# dc26-dev-board-apa102c.net
KiCad netlist of a schematic drawn in EAGLE
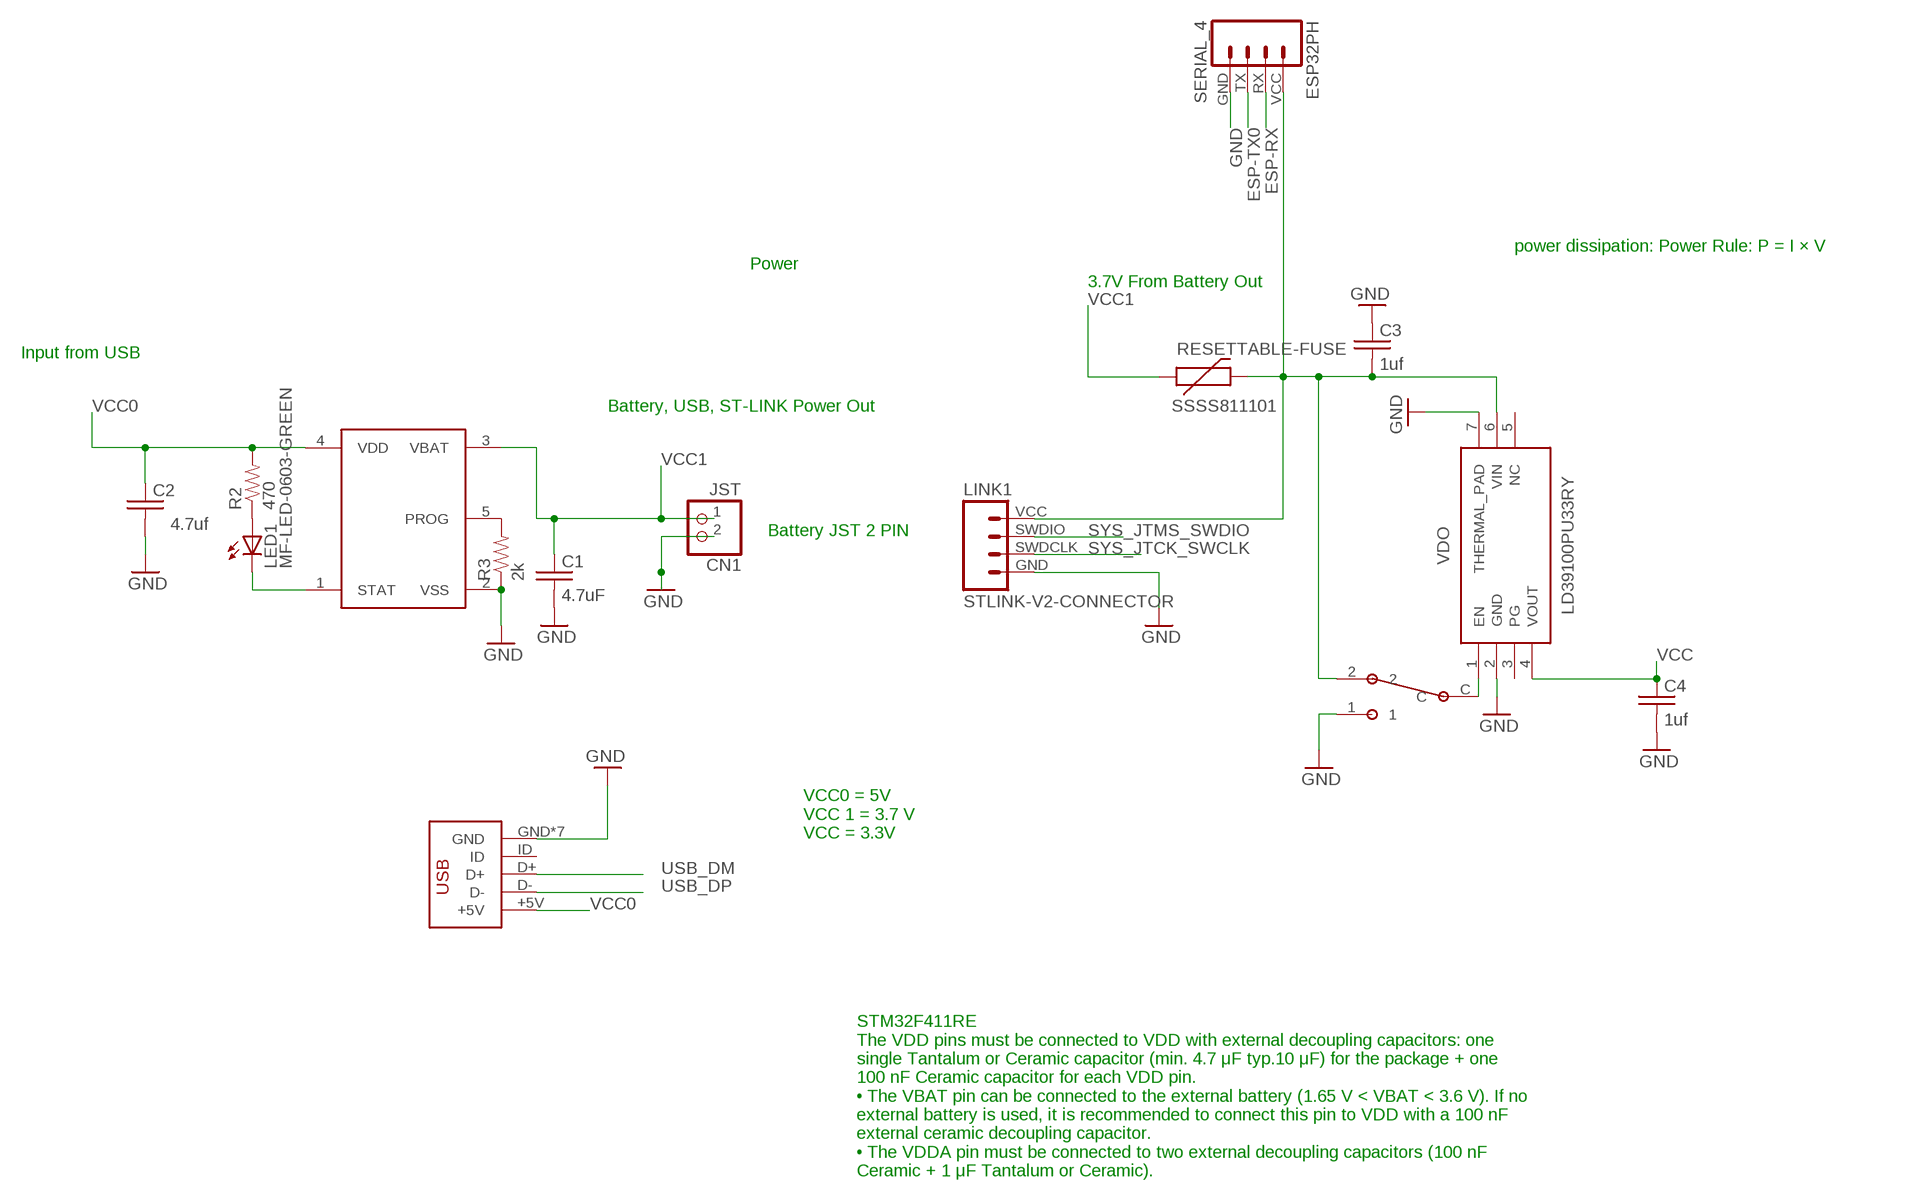
[diagram p0: schematic, sheet 1]
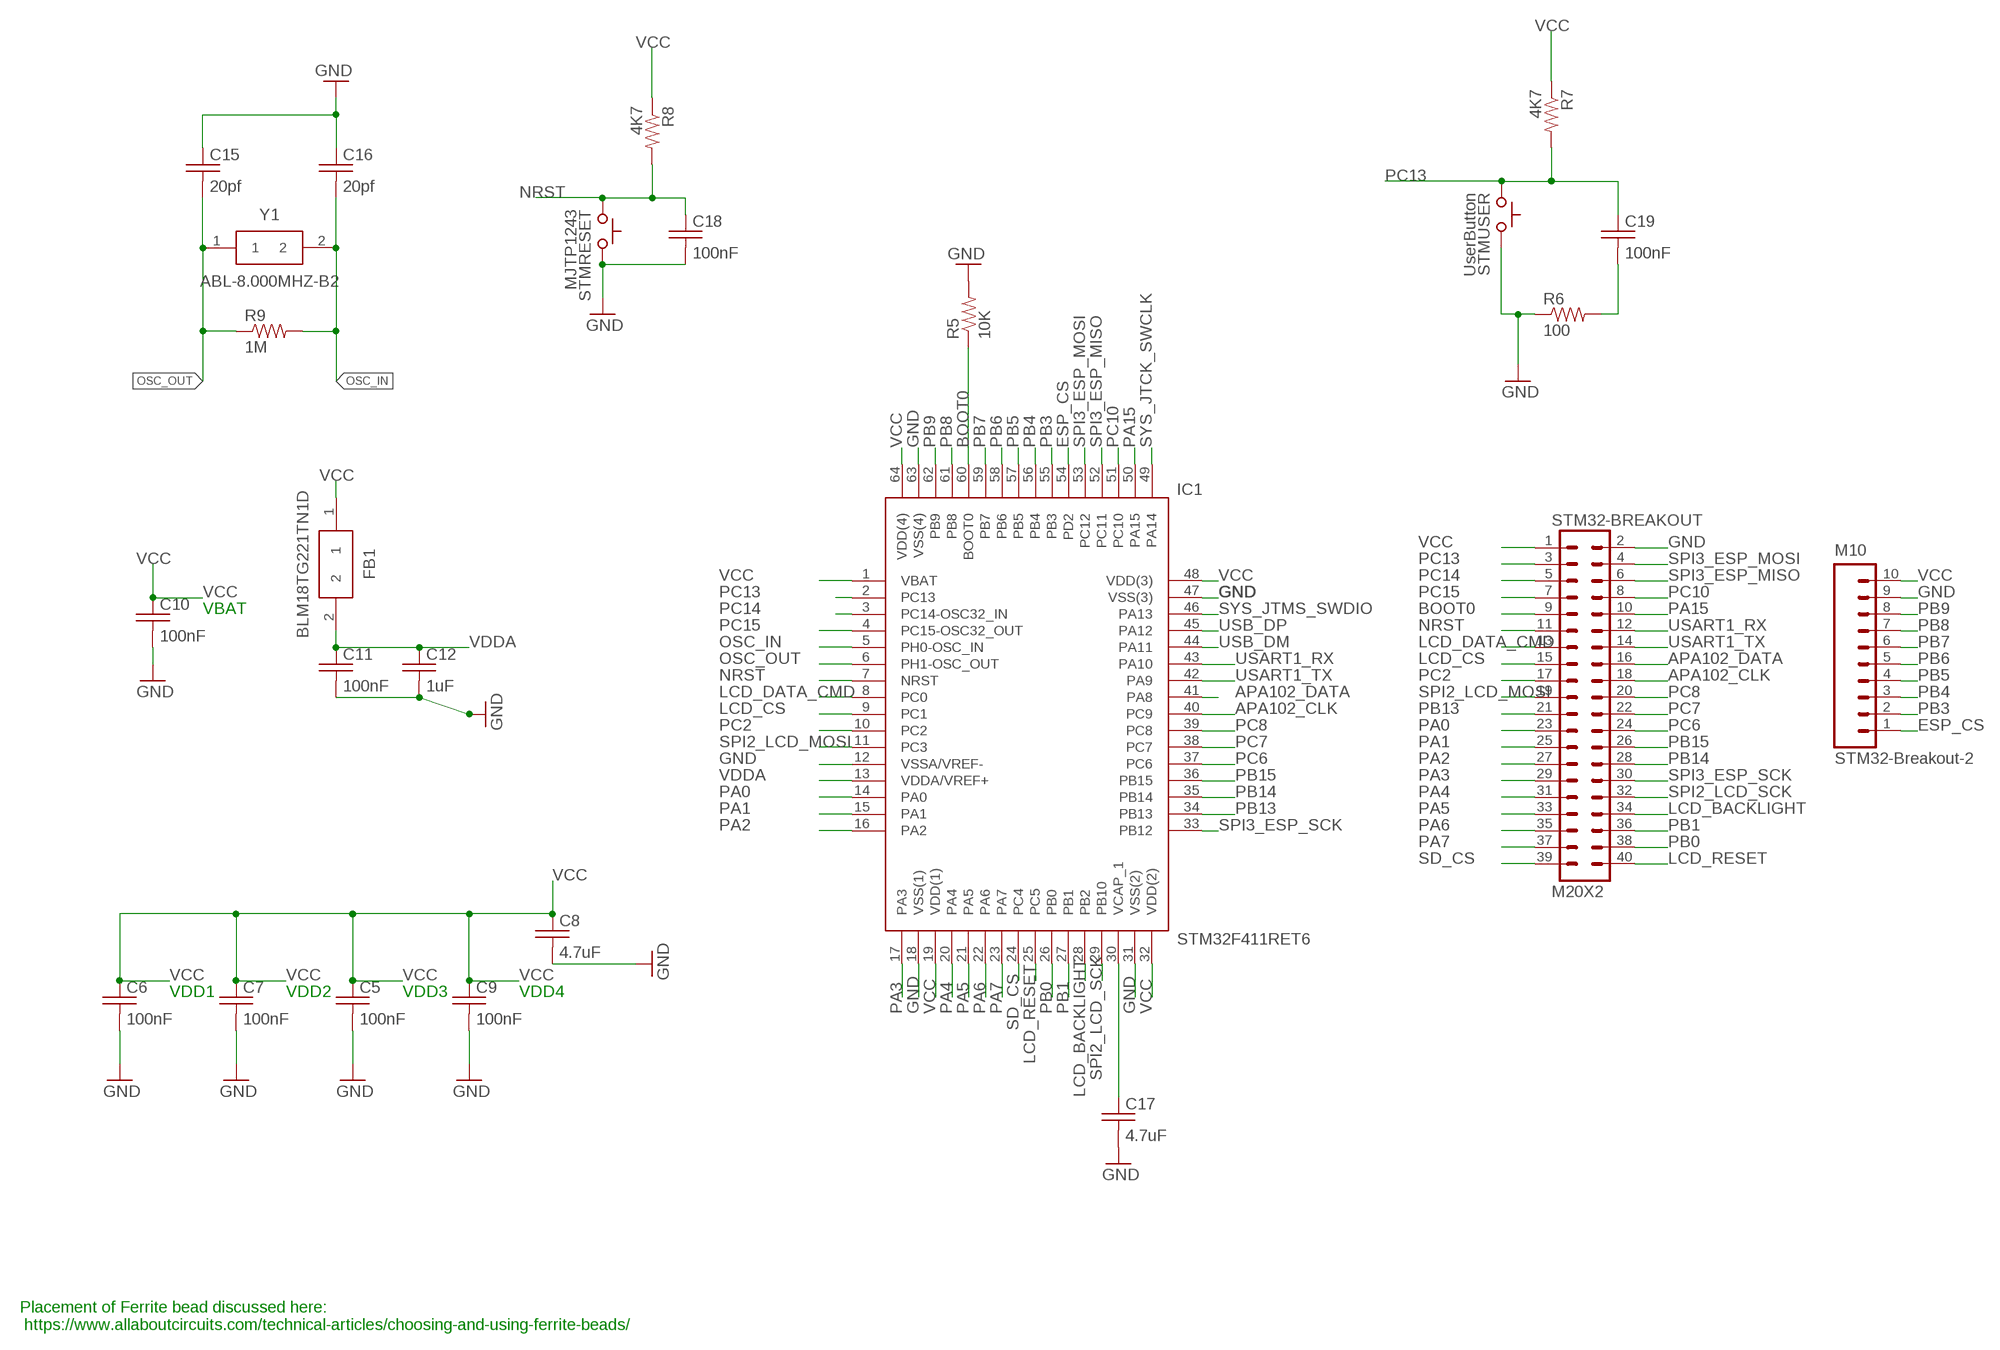
[diagram p1: schematic, sheet 2]
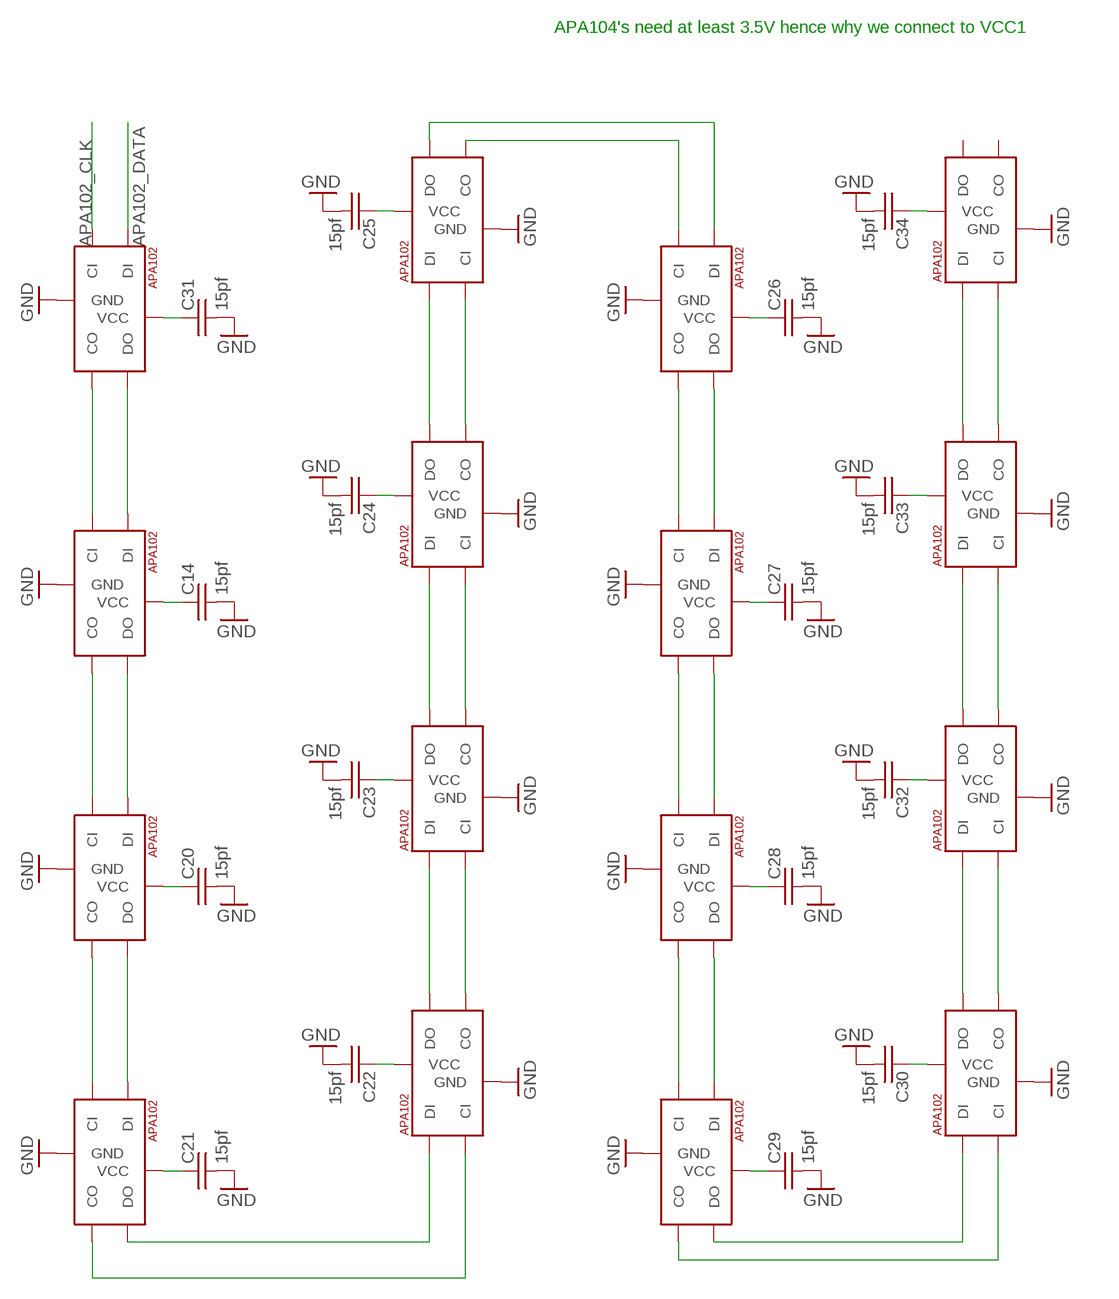
[diagram p2: schematic, sheet 3]
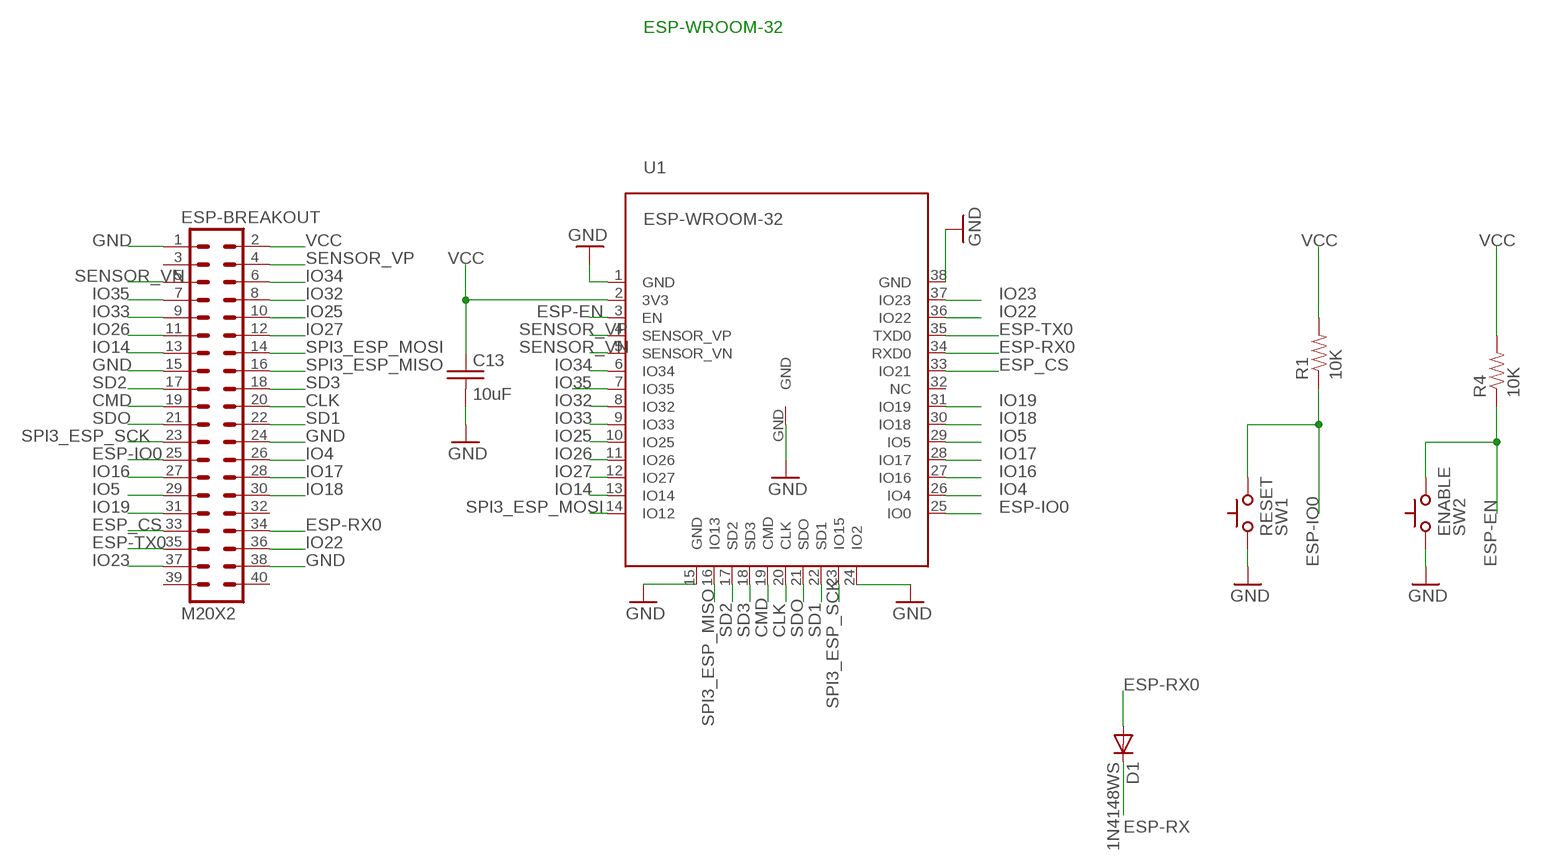
[diagram p3: schematic, sheet 4]
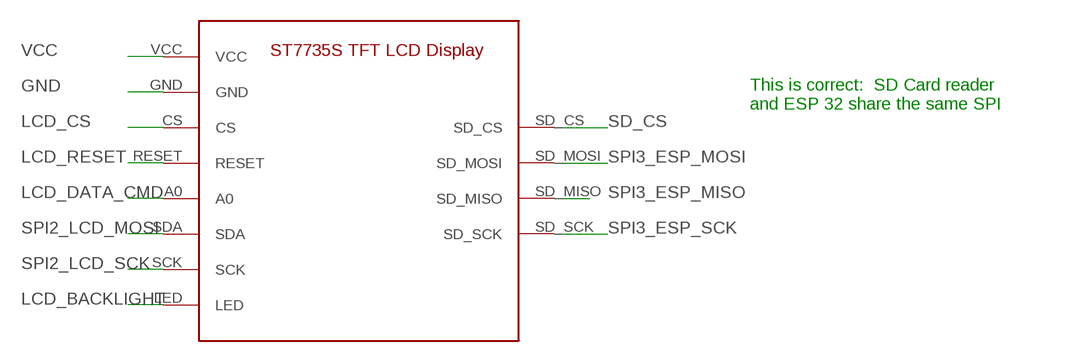
[diagram p4: schematic, sheet 5]
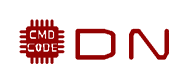
[diagram p5: schematic, sheet 6]
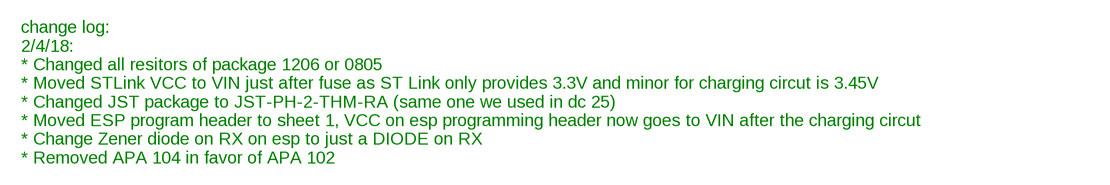
[diagram p6: schematic, sheet 7]

(export (version "E")
  (design (tool "Eeschema 10.0.6"))
  (components
    (comp (ref "C1")
      (value "4.7uF")
      (footprint "eagle-import:C0805")
      (libsource (lib "eagle-import") (part "C-USC0805"))
    )
    (comp (ref "C2")
      (value "4.7uf")
      (footprint "eagle-import:C0805")
      (libsource (lib "eagle-import") (part "C-USC0805"))
    )
    (comp (ref "C3")
      (value "1uf")
      (footprint "eagle-import:C0805")
      (libsource (lib "eagle-import") (part "C-USC0805"))
    )
    (comp (ref "C4")
      (value "1uf")
      (footprint "eagle-import:C0805")
      (libsource (lib "eagle-import") (part "C-USC0805"))
    )
    (comp (ref "CHARGING_CIRCUT")
      (value "MCP73831")
      (footprint "eagle-import:SOT23-5")
      (libsource (lib "eagle-import") (part "DS21984E"))
    )
    (comp (ref "CN1")
      (value "JST")
      (footprint "eagle-import:JST-PH-2-THM-RA")
      (libsource (lib "eagle-import") (part "JST_2PIN-THM-RA"))
    )
    (comp (ref "ESP32PH")
      (value "SERIAL_4")
      (footprint "eagle-import:SERIAL_HEADER_4")
      (libsource (lib "eagle-import") (part "SERIAL_4"))
    )
    (comp (ref "LED1")
      (value "MF-LED-0603-GREEN")
      (footprint "eagle-import:LED-1206")
      (libsource (lib "eagle-import") (part "LED1206"))
    )
    (comp (ref "LINK1")
      (value "STLINK-V2-CONNECTOR")
      (footprint "eagle-import:1X04")
      (libsource (lib "eagle-import") (part "STLINK-V2-CONNECTOR"))
    )
    (comp (ref "P1")
      (value "SSSS811101")
      (footprint "eagle-import:SPDT_SSAJ120100")
      (libsource (lib "eagle-import") (part "SWITCH_SPDT"))
    )
    (comp (ref "R2")
      (value "470")
      (footprint "eagle-import:0805")
      (libsource (lib "eagle-import") (part "RESISTOR0805-RES"))
    )
    (comp (ref "R3")
      (value "2k")
      (footprint "eagle-import:0805")
      (libsource (lib "eagle-import") (part "RESISTOR0805-RES"))
    )
    (comp (ref "RESETTABLE-FUSE")
      (value "SSSS811101")
      (footprint "eagle-import:PTC-1206")
      (libsource (lib "eagle-import") (part "PTCSMD"))
    )
    (comp (ref "USB")
      (value "DX4R005JJ2DX4R005JJ2")
      (footprint "eagle-import:DX4R005JJ2")
      (libsource (lib "eagle-import") (part "DX4R005JJ2DX4R005JJ2"))
    )
    (comp (ref "VDO")
      (value "LD39100PU33RY")
      (footprint "eagle-import:SON95P300X300X90-7N")
      (libsource (lib "eagle-import") (part "LD39100PU33RY"))
    )
    (comp (ref "U$2")
      (value "CMD_C0DE_LOGO")
      (footprint "eagle-import:CMD_C0DE_LOGO")
      (libsource (lib "eagle-import") (part "CMD_C0DE_LOGO"))
    )
    (comp (ref "U$3")
      (value "DARKNET_DD")
      (footprint "eagle-import:DARKNET_D")
      (libsource (lib "eagle-import") (part "DARKNET_DD"))
    )
    (comp (ref "U$4")
      (value "DARKNET_NN")
      (footprint "eagle-import:DARKNET_N")
      (libsource (lib "eagle-import") (part "DARKNET_NN"))
    )
    (comp (ref "U$1")
      (value "ST7735S_LCD_MODULE")
      (footprint "eagle-import:ST7735S_LCD_DISPLAY")
      (libsource (lib "eagle-import") (part "ST7735S_LCD_MODULE"))
    )
    (comp (ref "C13")
      (value "10uF")
      (footprint "eagle-import:C0805")
      (libsource (lib "eagle-import") (part "C-USC0805"))
    )
    (comp (ref "D1")
      (value "1N4148WS")
      (footprint "eagle-import:SOD-323")
      (libsource (lib "eagle-import") (part "DIODESOD"))
    )
    (comp (ref "ENABLE")
      (value "SW2")
      (footprint "eagle-import:TACTILE-2PIN-NARROW")
      (libsource (lib "eagle-import") (part "SWITCH_TACTILETACTILE-2PIN-NARROW"))
    )
    (comp (ref "ESP-BREAKOUT")
      (value "M20X2")
      (footprint "eagle-import:2X20")
      (libsource (lib "eagle-import") (part "M20X2"))
    )
    (comp (ref "R1")
      (value "10K")
      (footprint "eagle-import:0805")
      (libsource (lib "eagle-import") (part "RESISTOR0805-RES"))
    )
    (comp (ref "R4")
      (value "10K")
      (footprint "eagle-import:0805")
      (libsource (lib "eagle-import") (part "RESISTOR0805-RES"))
    )
    (comp (ref "RESET")
      (value "SW1")
      (footprint "eagle-import:TACTILE-2PIN-NARROW")
      (libsource (lib "eagle-import") (part "SWITCH_TACTILETACTILE-2PIN-NARROW"))
    )
    (comp (ref "U1")
      (value "ESP-WROOM-32")
      (footprint "eagle-import:ESP-WROOM-32")
      (libsource (lib "eagle-import") (part "ESP-WROOM-32"))
    )
    (comp (ref "C14")
      (value "15pf")
      (footprint "eagle-import:C0805")
      (libsource (lib "eagle-import") (part "C-USC0805"))
    )
    (comp (ref "C20")
      (value "15pf")
      (footprint "eagle-import:C0805")
      (libsource (lib "eagle-import") (part "C-USC0805"))
    )
    (comp (ref "C21")
      (value "15pf")
      (footprint "eagle-import:C0805")
      (libsource (lib "eagle-import") (part "C-USC0805"))
    )
    (comp (ref "C22")
      (value "15pf")
      (footprint "eagle-import:C0805")
      (libsource (lib "eagle-import") (part "C-USC0805"))
    )
    (comp (ref "C23")
      (value "15pf")
      (footprint "eagle-import:C0805")
      (libsource (lib "eagle-import") (part "C-USC0805"))
    )
    (comp (ref "C24")
      (value "15pf")
      (footprint "eagle-import:C0805")
      (libsource (lib "eagle-import") (part "C-USC0805"))
    )
    (comp (ref "C25")
      (value "15pf")
      (footprint "eagle-import:C0805")
      (libsource (lib "eagle-import") (part "C-USC0805"))
    )
    (comp (ref "C26")
      (value "15pf")
      (footprint "eagle-import:C0805")
      (libsource (lib "eagle-import") (part "C-USC0805"))
    )
    (comp (ref "C27")
      (value "15pf")
      (footprint "eagle-import:C0805")
      (libsource (lib "eagle-import") (part "C-USC0805"))
    )
    (comp (ref "C28")
      (value "15pf")
      (footprint "eagle-import:C0805")
      (libsource (lib "eagle-import") (part "C-USC0805"))
    )
    (comp (ref "C29")
      (value "15pf")
      (footprint "eagle-import:C0805")
      (libsource (lib "eagle-import") (part "C-USC0805"))
    )
    (comp (ref "C30")
      (value "15pf")
      (footprint "eagle-import:C0805")
      (libsource (lib "eagle-import") (part "C-USC0805"))
    )
    (comp (ref "C31")
      (value "15pf")
      (footprint "eagle-import:C0805")
      (libsource (lib "eagle-import") (part "C-USC0805"))
    )
    (comp (ref "C32")
      (value "15pf")
      (footprint "eagle-import:C0805")
      (libsource (lib "eagle-import") (part "C-USC0805"))
    )
    (comp (ref "C33")
      (value "15pf")
      (footprint "eagle-import:C0805")
      (libsource (lib "eagle-import") (part "C-USC0805"))
    )
    (comp (ref "C34")
      (value "15pf")
      (footprint "eagle-import:C0805")
      (libsource (lib "eagle-import") (part "C-USC0805"))
    )
    (comp (ref "U$5")
      (value "APA1025050")
      (footprint "eagle-import:APA102_5050")
      (libsource (lib "eagle-import") (part "APA1025050"))
    )
    (comp (ref "U$6")
      (value "APA1025050")
      (footprint "eagle-import:APA102_5050")
      (libsource (lib "eagle-import") (part "APA1025050"))
    )
    (comp (ref "U$7")
      (value "APA1025050")
      (footprint "eagle-import:APA102_5050")
      (libsource (lib "eagle-import") (part "APA1025050"))
    )
    (comp (ref "U$8")
      (value "APA1025050")
      (footprint "eagle-import:APA102_5050")
      (libsource (lib "eagle-import") (part "APA1025050"))
    )
    (comp (ref "U$9")
      (value "APA1025050")
      (footprint "eagle-import:APA102_5050")
      (libsource (lib "eagle-import") (part "APA1025050"))
    )
    (comp (ref "U$10")
      (value "APA1025050")
      (footprint "eagle-import:APA102_5050")
      (libsource (lib "eagle-import") (part "APA1025050"))
    )
    (comp (ref "U$11")
      (value "APA1025050")
      (footprint "eagle-import:APA102_5050")
      (libsource (lib "eagle-import") (part "APA1025050"))
    )
    (comp (ref "U$12")
      (value "APA1025050")
      (footprint "eagle-import:APA102_5050")
      (libsource (lib "eagle-import") (part "APA1025050"))
    )
    (comp (ref "U$13")
      (value "APA1025050")
      (footprint "eagle-import:APA102_5050")
      (libsource (lib "eagle-import") (part "APA1025050"))
    )
    (comp (ref "U$14")
      (value "APA1025050")
      (footprint "eagle-import:APA102_5050")
      (libsource (lib "eagle-import") (part "APA1025050"))
    )
    (comp (ref "U$15")
      (value "APA1025050")
      (footprint "eagle-import:APA102_5050")
      (libsource (lib "eagle-import") (part "APA1025050"))
    )
    (comp (ref "U$16")
      (value "APA1025050")
      (footprint "eagle-import:APA102_5050")
      (libsource (lib "eagle-import") (part "APA1025050"))
    )
    (comp (ref "U$17")
      (value "APA1025050")
      (footprint "eagle-import:APA102_5050")
      (libsource (lib "eagle-import") (part "APA1025050"))
    )
    (comp (ref "U$18")
      (value "APA1025050")
      (footprint "eagle-import:APA102_5050")
      (libsource (lib "eagle-import") (part "APA1025050"))
    )
    (comp (ref "U$19")
      (value "APA1025050")
      (footprint "eagle-import:APA102_5050")
      (libsource (lib "eagle-import") (part "APA1025050"))
    )
    (comp (ref "U$20")
      (value "APA1025050")
      (footprint "eagle-import:APA102_5050")
      (libsource (lib "eagle-import") (part "APA1025050"))
    )
    (comp (ref "C5")
      (value "100nF")
      (footprint "eagle-import:C0805")
      (libsource (lib "eagle-import") (part "C-USC0805"))
    )
    (comp (ref "C6")
      (value "100nF")
      (footprint "eagle-import:C0805")
      (libsource (lib "eagle-import") (part "C-USC0805"))
    )
    (comp (ref "C7")
      (value "100nF")
      (footprint "eagle-import:C0805")
      (libsource (lib "eagle-import") (part "C-USC0805"))
    )
    (comp (ref "C8")
      (value "4.7uF")
      (footprint "eagle-import:C0805")
      (libsource (lib "eagle-import") (part "C-USC0805"))
    )
    (comp (ref "C9")
      (value "100nF")
      (footprint "eagle-import:C0805")
      (libsource (lib "eagle-import") (part "C-USC0805"))
    )
    (comp (ref "C10")
      (value "100nF")
      (footprint "eagle-import:C0805")
      (libsource (lib "eagle-import") (part "C-USC0805"))
    )
    (comp (ref "C11")
      (value "100nF")
      (footprint "eagle-import:C0805")
      (libsource (lib "eagle-import") (part "C-USC0805"))
    )
    (comp (ref "C12")
      (value "1uF")
      (footprint "eagle-import:C0805")
      (libsource (lib "eagle-import") (part "C-USC0805"))
    )
    (comp (ref "C15")
      (value "20pf")
      (footprint "eagle-import:C0805")
      (libsource (lib "eagle-import") (part "C-USC0805"))
    )
    (comp (ref "C16")
      (value "20pf")
      (footprint "eagle-import:C0805")
      (libsource (lib "eagle-import") (part "C-USC0805"))
    )
    (comp (ref "C17")
      (value "4.7uF")
      (footprint "eagle-import:C0805")
      (libsource (lib "eagle-import") (part "C-USC0805"))
    )
    (comp (ref "C18")
      (value "100nF")
      (footprint "eagle-import:C0805")
      (libsource (lib "eagle-import") (part "C-USC0805"))
    )
    (comp (ref "C19")
      (value "100nF")
      (footprint "eagle-import:C0805")
      (libsource (lib "eagle-import") (part "C-USC0805"))
    )
    (comp (ref "FB1")
      (value "BLM18TG221TN1D")
      (footprint "eagle-import:BEADC1608X75N")
      (fields (field (name "RS_PART_NUMBER") "6197526"))
      (libsource (lib "eagle-import") (part "BLM18TG221TN1D"))
    )
    (comp (ref "IC1")
      (value "STM32F411RET6")
      (footprint "eagle-import:QFP50P1200X1200X160-64N")
      (fields (field (name "RS_PART_NUMBER") "1106617P"))
      (libsource (lib "eagle-import") (part "STM32F411RET6"))
    )
    (comp (ref "M10")
      (value "STM32-Breakout-2")
      (footprint "eagle-import:1X10")
      (libsource (lib "eagle-import") (part "M10SILK_FEMALE_PTH"))
    )
    (comp (ref "R5")
      (value "10K")
      (footprint "eagle-import:0805")
      (libsource (lib "eagle-import") (part "RESISTOR0805-RES"))
    )
    (comp (ref "R6")
      (value "100")
      (footprint "eagle-import:0805")
      (libsource (lib "eagle-import") (part "RESISTOR0805-RES"))
    )
    (comp (ref "R7")
      (value "4K7")
      (footprint "eagle-import:0805")
      (libsource (lib "eagle-import") (part "RESISTOR0805-RES"))
    )
    (comp (ref "R8")
      (value "4K7")
      (footprint "eagle-import:0805")
      (libsource (lib "eagle-import") (part "RESISTOR0805-RES"))
    )
    (comp (ref "R9")
      (value "1M")
      (footprint "eagle-import:0805")
      (libsource (lib "eagle-import") (part "RESISTOR0805-RES"))
    )
    (comp (ref "STM32-BREAKOUT")
      (value "M20X2")
      (footprint "eagle-import:2X20")
      (libsource (lib "eagle-import") (part "M20X2"))
    )
    (comp (ref "STMRESET")
      (value "MJTP1243")
      (footprint "eagle-import:TACTILE-2PIN-NARROW")
      (libsource (lib "eagle-import") (part "SWITCH_TACTILETACTILE-2PIN-NARROW"))
    )
    (comp (ref "STMUSER")
      (value "UserButton")
      (footprint "eagle-import:TACTILE-2PIN-NARROW")
      (libsource (lib "eagle-import") (part "SWITCH_TACTILETACTILE-2PIN-NARROW"))
    )
    (comp (ref "Y1")
      (value "ABL-8.000MHZ-B2")
      (footprint "eagle-import:HC_49US_(AT49)PTH")
      (libsource (lib "eagle-import") (part "ABL-8.000MHZ-B2"))
    )
  )
  (nets
    (net (code "1") (name "APA102_CLK") (class "Default")
      (node (ref "IC1") (pin "40") (pinfunction "PC9_40") (pintype "passive"))
      (node (ref "STM32-BREAKOUT") (pin "18") (pinfunction "18_18") (pintype "passive"))
      (node (ref "U$8") (pin "5") (pinfunction "CI_5") (pintype "bidirectional"))
    )
    (net (code "2") (name "APA102_DATA") (class "Default")
      (node (ref "IC1") (pin "41") (pinfunction "PA8_41") (pintype "passive"))
      (node (ref "STM32-BREAKOUT") (pin "16") (pinfunction "16_16") (pintype "passive"))
      (node (ref "U$8") (pin "4") (pinfunction "DI_4") (pintype "bidirectional"))
    )
    (net (code "3") (name "BOOT0") (class "Default")
      (node (ref "IC1") (pin "60") (pinfunction "BOOT0_60") (pintype "passive"))
      (node (ref "R5") (pin "1") (pinfunction "1_1") (pintype "passive"))
      (node (ref "STM32-BREAKOUT") (pin "9") (pinfunction "9_9") (pintype "passive"))
    )
    (net (code "4") (name "CLK") (class "Default")
      (node (ref "ESP-BREAKOUT") (pin "20") (pinfunction "20_20") (pintype "passive"))
      (node (ref "U1") (pin "20") (pinfunction "CLK_20") (pintype "bidirectional"))
    )
    (net (code "5") (name "CMD") (class "Default")
      (node (ref "ESP-BREAKOUT") (pin "19") (pinfunction "19_19") (pintype "passive"))
      (node (ref "U1") (pin "19") (pinfunction "CMD_19") (pintype "bidirectional"))
    )
    (net (code "6") (name "ESP-EN") (class "Default")
      (node (ref "ENABLE") (pin "P$1") (pinfunction "A_P$1") (pintype "passive"))
      (node (ref "R4") (pin "1") (pinfunction "1_1") (pintype "passive"))
      (node (ref "U1") (pin "3") (pinfunction "EN_3") (pintype "bidirectional"))
    )
    (net (code "7") (name "ESP-IO0") (class "Default")
      (node (ref "ESP-BREAKOUT") (pin "25") (pinfunction "25_25") (pintype "passive"))
      (node (ref "R1") (pin "1") (pinfunction "1_1") (pintype "passive"))
      (node (ref "RESET") (pin "P$1") (pinfunction "A_P$1") (pintype "passive"))
      (node (ref "U1") (pin "25") (pinfunction "IO0_25") (pintype "bidirectional"))
    )
    (net (code "8") (name "ESP-RX") (class "Default")
      (node (ref "D1") (pin "1") (pinfunction "C_1") (pintype "passive"))
      (node (ref "ESP32PH") (pin "RX") (pinfunction "RX_RX") (pintype "bidirectional"))
    )
    (net (code "9") (name "ESP-RX0") (class "Default")
      (node (ref "D1") (pin "2") (pinfunction "A_2") (pintype "passive"))
      (node (ref "ESP-BREAKOUT") (pin "34") (pinfunction "34_34") (pintype "passive"))
      (node (ref "U1") (pin "34") (pinfunction "RXD0_34") (pintype "bidirectional"))
    )
    (net (code "10") (name "ESP-TX0") (class "Default")
      (node (ref "ESP-BREAKOUT") (pin "35") (pinfunction "35_35") (pintype "passive"))
      (node (ref "ESP32PH") (pin "TX") (pinfunction "TX_TX") (pintype "input"))
      (node (ref "U1") (pin "35") (pinfunction "TXD0_35") (pintype "bidirectional"))
    )
    (net (code "11") (name "ESP_CS") (class "Default")
      (node (ref "ESP-BREAKOUT") (pin "33") (pinfunction "33_33") (pintype "passive"))
      (node (ref "IC1") (pin "54") (pinfunction "PD2_54") (pintype "passive"))
      (node (ref "M10") (pin "1") (pinfunction "1_1") (pintype "passive"))
      (node (ref "U1") (pin "33") (pinfunction "IO21_33") (pintype "bidirectional"))
    )
    (net (code "12") (name "GND") (class "Default")
      (node (ref "C1") (pin "2") (pinfunction "2_2") (pintype "passive"))
      (node (ref "C10") (pin "2") (pinfunction "2_2") (pintype "passive"))
      (node (ref "C11") (pin "2") (pinfunction "2_2") (pintype "passive"))
      (node (ref "C12") (pin "2") (pinfunction "2_2") (pintype "passive"))
      (node (ref "C13") (pin "2") (pinfunction "2_2") (pintype "passive"))
      (node (ref "C14") (pin "2") (pinfunction "2_2") (pintype "passive"))
      (node (ref "C15") (pin "1") (pinfunction "1_1") (pintype "passive"))
      (node (ref "C16") (pin "1") (pinfunction "1_1") (pintype "passive"))
      (node (ref "C17") (pin "2") (pinfunction "2_2") (pintype "passive"))
      (node (ref "C18") (pin "2") (pinfunction "2_2") (pintype "passive"))
      (node (ref "C2") (pin "2") (pinfunction "2_2") (pintype "passive"))
      (node (ref "C20") (pin "2") (pinfunction "2_2") (pintype "passive"))
      (node (ref "C21") (pin "2") (pinfunction "2_2") (pintype "passive"))
      (node (ref "C22") (pin "2") (pinfunction "2_2") (pintype "passive"))
      (node (ref "C23") (pin "2") (pinfunction "2_2") (pintype "passive"))
      (node (ref "C24") (pin "2") (pinfunction "2_2") (pintype "passive"))
      (node (ref "C25") (pin "2") (pinfunction "2_2") (pintype "passive"))
      (node (ref "C26") (pin "2") (pinfunction "2_2") (pintype "passive"))
      (node (ref "C27") (pin "2") (pinfunction "2_2") (pintype "passive"))
      (node (ref "C28") (pin "2") (pinfunction "2_2") (pintype "passive"))
      (node (ref "C29") (pin "2") (pinfunction "2_2") (pintype "passive"))
      (node (ref "C3") (pin "1") (pinfunction "1_1") (pintype "passive"))
      (node (ref "C30") (pin "2") (pinfunction "2_2") (pintype "passive"))
      (node (ref "C31") (pin "2") (pinfunction "2_2") (pintype "passive"))
      (node (ref "C32") (pin "2") (pinfunction "2_2") (pintype "passive"))
      (node (ref "C33") (pin "2") (pinfunction "2_2") (pintype "passive"))
      (node (ref "C34") (pin "2") (pinfunction "2_2") (pintype "passive"))
      (node (ref "C4") (pin "2") (pinfunction "2_2") (pintype "passive"))
      (node (ref "C5") (pin "2") (pinfunction "2_2") (pintype "passive"))
      (node (ref "C6") (pin "2") (pinfunction "2_2") (pintype "passive"))
      (node (ref "C7") (pin "2") (pinfunction "2_2") (pintype "passive"))
      (node (ref "C8") (pin "2") (pinfunction "2_2") (pintype "passive"))
      (node (ref "C9") (pin "2") (pinfunction "2_2") (pintype "passive"))
      (node (ref "CHARGING_CIRCUT") (pin "2") (pinfunction "VSS_2") (pintype "bidirectional"))
      (node (ref "CN1") (pin "2") (pinfunction "1_2") (pintype "passive"))
      (node (ref "ENABLE") (pin "P$2") (pinfunction "C_P$2") (pintype "passive"))
      (node (ref "ESP-BREAKOUT") (pin "1") (pinfunction "1_1") (pintype "passive"))
      (node (ref "ESP-BREAKOUT") (pin "15") (pinfunction "15_15") (pintype "passive"))
      (node (ref "ESP-BREAKOUT") (pin "24") (pinfunction "24_24") (pintype "passive"))
      (node (ref "ESP-BREAKOUT") (pin "38") (pinfunction "38_38") (pintype "passive"))
      (node (ref "ESP32PH") (pin "GND") (pinfunction "GND_GND") (pintype "power_in"))
      (node (ref "IC1") (pin "12") (pinfunction "VSSA/VREF-_12") (pintype "passive"))
      (node (ref "IC1") (pin "18") (pinfunction "VSS(1)_18") (pintype "passive"))
      (node (ref "IC1") (pin "31") (pinfunction "VSS(2)_31") (pintype "passive"))
      (node (ref "IC1") (pin "47") (pinfunction "VSS(3)_47") (pintype "passive"))
      (node (ref "IC1") (pin "63") (pinfunction "VSS(4)_63") (pintype "passive"))
      (node (ref "LINK1") (pin "GND") (pinfunction "GND_GND") (pintype "power_in"))
      (node (ref "M10") (pin "9") (pinfunction "9_9") (pintype "passive"))
      (node (ref "P1") (pin "1") (pinfunction "1_1") (pintype "bidirectional"))
      (node (ref "R3") (pin "1") (pinfunction "1_1") (pintype "passive"))
      (node (ref "R5") (pin "2") (pinfunction "2_2") (pintype "passive"))
      (node (ref "R6") (pin "1") (pinfunction "1_1") (pintype "passive"))
      (node (ref "RESET") (pin "P$2") (pinfunction "C_P$2") (pintype "passive"))
      (node (ref "STM32-BREAKOUT") (pin "2") (pinfunction "2_2") (pintype "passive"))
      (node (ref "STMRESET") (pin "P$1") (pinfunction "A_P$1") (pintype "passive"))
      (node (ref "STMUSER") (pin "P$1") (pinfunction "A_P$1") (pintype "passive"))
      (node (ref "U$1") (pin "GND") (pinfunction "GND_GND") (pintype "bidirectional"))
      (node (ref "U$10") (pin "6") (pinfunction "GND_6") (pintype "bidirectional"))
      (node (ref "U$11") (pin "6") (pinfunction "GND_6") (pintype "bidirectional"))
      (node (ref "U$12") (pin "6") (pinfunction "GND_6") (pintype "bidirectional"))
      (node (ref "U$13") (pin "6") (pinfunction "GND_6") (pintype "bidirectional"))
      (node (ref "U$14") (pin "6") (pinfunction "GND_6") (pintype "bidirectional"))
      (node (ref "U$15") (pin "6") (pinfunction "GND_6") (pintype "bidirectional"))
      (node (ref "U$16") (pin "6") (pinfunction "GND_6") (pintype "bidirectional"))
      (node (ref "U$17") (pin "6") (pinfunction "GND_6") (pintype "bidirectional"))
      (node (ref "U$18") (pin "6") (pinfunction "GND_6") (pintype "bidirectional"))
      (node (ref "U$19") (pin "6") (pinfunction "GND_6") (pintype "bidirectional"))
      (node (ref "U$20") (pin "6") (pinfunction "GND_6") (pintype "bidirectional"))
      (node (ref "U$5") (pin "6") (pinfunction "GND_6") (pintype "bidirectional"))
      (node (ref "U$6") (pin "6") (pinfunction "GND_6") (pintype "bidirectional"))
      (node (ref "U$7") (pin "6") (pinfunction "GND_6") (pintype "bidirectional"))
      (node (ref "U$8") (pin "6") (pinfunction "GND_6") (pintype "bidirectional"))
      (node (ref "U$9") (pin "6") (pinfunction "GND_6") (pintype "bidirectional"))
      (node (ref "U1") (pin "1") (pinfunction "GND_1") (pintype "bidirectional"))
      (node (ref "U1") (pin "15") (pinfunction "GND_15") (pintype "bidirectional"))
      (node (ref "U1") (pin "24") (pinfunction "IO2_24") (pintype "bidirectional"))
      (node (ref "U1") (pin "38") (pinfunction "GND_38") (pintype "bidirectional"))
      (node (ref "U1") (pin "GND") (pinfunction "GND_GND") (pintype "bidirectional"))
      (node (ref "USB") (pin "GND") (pinfunction "GND_GND") (pintype "bidirectional"))
      (node (ref "USB") (pin "P$10") (pinfunction "GND_P$10") (pintype "bidirectional"))
      (node (ref "USB") (pin "P$11") (pinfunction "GND_P$11") (pintype "bidirectional"))
      (node (ref "USB") (pin "P$6") (pinfunction "GND_P$6") (pintype "bidirectional"))
      (node (ref "USB") (pin "P$7") (pinfunction "GND_P$7") (pintype "bidirectional"))
      (node (ref "USB") (pin "P$8") (pinfunction "GND_P$8") (pintype "bidirectional"))
      (node (ref "USB") (pin "P$9") (pinfunction "GND_P$9") (pintype "bidirectional"))
      (node (ref "VDO") (pin "2") (pinfunction "GND_2") (pintype "passive"))
      (node (ref "VDO") (pin "7") (pinfunction "THERMAL_PAD_7") (pintype "passive"))
    )
    (net (code "13") (name "IO4") (class "Default")
      (node (ref "ESP-BREAKOUT") (pin "26") (pinfunction "26_26") (pintype "passive"))
      (node (ref "U1") (pin "26") (pinfunction "IO4_26") (pintype "bidirectional"))
    )
    (net (code "14") (name "IO5") (class "Default")
      (node (ref "ESP-BREAKOUT") (pin "29") (pinfunction "29_29") (pintype "passive"))
      (node (ref "U1") (pin "29") (pinfunction "IO5_29") (pintype "bidirectional"))
    )
    (net (code "15") (name "IO14") (class "Default")
      (node (ref "ESP-BREAKOUT") (pin "13") (pinfunction "13_13") (pintype "passive"))
      (node (ref "U1") (pin "13") (pinfunction "IO14_13") (pintype "bidirectional"))
    )
    (net (code "16") (name "IO16") (class "Default")
      (node (ref "ESP-BREAKOUT") (pin "27") (pinfunction "27_27") (pintype "passive"))
      (node (ref "U1") (pin "27") (pinfunction "IO16_27") (pintype "bidirectional"))
    )
    (net (code "17") (name "IO17") (class "Default")
      (node (ref "ESP-BREAKOUT") (pin "28") (pinfunction "28_28") (pintype "passive"))
      (node (ref "U1") (pin "28") (pinfunction "IO17_28") (pintype "bidirectional"))
    )
    (net (code "18") (name "IO18") (class "Default")
      (node (ref "ESP-BREAKOUT") (pin "30") (pinfunction "30_30") (pintype "passive"))
      (node (ref "U1") (pin "30") (pinfunction "IO18_30") (pintype "bidirectional"))
    )
    (net (code "19") (name "IO19") (class "Default")
      (node (ref "ESP-BREAKOUT") (pin "31") (pinfunction "31_31") (pintype "passive"))
      (node (ref "U1") (pin "31") (pinfunction "IO19_31") (pintype "bidirectional"))
    )
    (net (code "20") (name "IO22") (class "Default")
      (node (ref "ESP-BREAKOUT") (pin "36") (pinfunction "36_36") (pintype "passive"))
      (node (ref "U1") (pin "36") (pinfunction "IO22_36") (pintype "bidirectional"))
    )
    (net (code "21") (name "IO23") (class "Default")
      (node (ref "ESP-BREAKOUT") (pin "37") (pinfunction "37_37") (pintype "passive"))
      (node (ref "U1") (pin "37") (pinfunction "IO23_37") (pintype "bidirectional"))
    )
    (net (code "22") (name "IO25") (class "Default")
      (node (ref "ESP-BREAKOUT") (pin "10") (pinfunction "10_10") (pintype "passive"))
      (node (ref "U1") (pin "10") (pinfunction "IO25_10") (pintype "bidirectional"))
    )
    (net (code "23") (name "IO26") (class "Default")
      (node (ref "ESP-BREAKOUT") (pin "11") (pinfunction "11_11") (pintype "passive"))
      (node (ref "U1") (pin "11") (pinfunction "IO26_11") (pintype "bidirectional"))
    )
    (net (code "24") (name "IO27") (class "Default")
      (node (ref "ESP-BREAKOUT") (pin "12") (pinfunction "12_12") (pintype "passive"))
      (node (ref "U1") (pin "12") (pinfunction "IO27_12") (pintype "bidirectional"))
    )
    (net (code "25") (name "IO32") (class "Default")
      (node (ref "ESP-BREAKOUT") (pin "8") (pinfunction "8_8") (pintype "passive"))
      (node (ref "U1") (pin "8") (pinfunction "IO32_8") (pintype "bidirectional"))
    )
    (net (code "26") (name "IO33") (class "Default")
      (node (ref "ESP-BREAKOUT") (pin "9") (pinfunction "9_9") (pintype "passive"))
      (node (ref "U1") (pin "9") (pinfunction "IO33_9") (pintype "bidirectional"))
    )
    (net (code "27") (name "IO34") (class "Default")
      (node (ref "ESP-BREAKOUT") (pin "6") (pinfunction "6_6") (pintype "passive"))
      (node (ref "U1") (pin "6") (pinfunction "IO34_6") (pintype "bidirectional"))
    )
    (net (code "28") (name "IO35") (class "Default")
      (node (ref "ESP-BREAKOUT") (pin "7") (pinfunction "7_7") (pintype "passive"))
      (node (ref "U1") (pin "7") (pinfunction "IO35_7") (pintype "bidirectional"))
    )
    (net (code "29") (name "LCD_BACKLIGHT") (class "Default")
      (node (ref "IC1") (pin "28") (pinfunction "PB2_28") (pintype "passive"))
      (node (ref "STM32-BREAKOUT") (pin "34") (pinfunction "34_34") (pintype "passive"))
      (node (ref "U$1") (pin "LED") (pinfunction "LED_LED") (pintype "bidirectional"))
    )
    (net (code "30") (name "LCD_CS") (class "Default")
      (node (ref "IC1") (pin "9") (pinfunction "PC1_9") (pintype "passive"))
      (node (ref "STM32-BREAKOUT") (pin "15") (pinfunction "15_15") (pintype "passive"))
      (node (ref "U$1") (pin "CS") (pinfunction "CS_CS") (pintype "bidirectional"))
    )
    (net (code "31") (name "LCD_DATA_CMD") (class "Default")
      (node (ref "IC1") (pin "8") (pinfunction "PC0_8") (pintype "passive"))
      (node (ref "STM32-BREAKOUT") (pin "13") (pinfunction "13_13") (pintype "passive"))
      (node (ref "U$1") (pin "A0") (pinfunction "A0_A0") (pintype "bidirectional"))
    )
    (net (code "32") (name "LCD_RESET") (class "Default")
      (node (ref "IC1") (pin "25") (pinfunction "PC5_25") (pintype "passive"))
      (node (ref "STM32-BREAKOUT") (pin "40") (pinfunction "40_40") (pintype "passive"))
      (node (ref "U$1") (pin "RESET") (pinfunction "RESET_RESET") (pintype "bidirectional"))
    )
    (net (code "33") (name "NRST") (class "Default")
      (node (ref "C18") (pin "1") (pinfunction "1_1") (pintype "passive"))
      (node (ref "IC1") (pin "7") (pinfunction "NRST_7") (pintype "passive"))
      (node (ref "R8") (pin "2") (pinfunction "2_2") (pintype "passive"))
      (node (ref "STM32-BREAKOUT") (pin "11") (pinfunction "11_11") (pintype "passive"))
      (node (ref "STMRESET") (pin "P$2") (pinfunction "C_P$2") (pintype "passive"))
    )
    (net (code "34") (name "Net-(C19-Pad2)") (class "Default")
      (node (ref "C19") (pin "2") (pinfunction "2_2") (pintype "passive"))
      (node (ref "R6") (pin "2") (pinfunction "2_2") (pintype "passive"))
    )
    (net (code "35") (name "Net-(CHARGING_CIRCUT-PROG)") (class "Default")
      (node (ref "CHARGING_CIRCUT") (pin "5") (pinfunction "PROG_5") (pintype "bidirectional"))
      (node (ref "R3") (pin "2") (pinfunction "2_2") (pintype "passive"))
    )
    (net (code "36") (name "Net-(CHARGING_CIRCUT-STAT)") (class "Default")
      (node (ref "CHARGING_CIRCUT") (pin "1") (pinfunction "STAT_1") (pintype "bidirectional"))
      (node (ref "LED1") (pin "C") (pinfunction "C_C") (pintype "output"))
    )
    (net (code "37") (name "Net-(IC1-VCAP_1)") (class "Default")
      (node (ref "C17") (pin "1") (pinfunction "1_1") (pintype "passive"))
      (node (ref "IC1") (pin "30") (pinfunction "VCAP_1_30") (pintype "passive"))
    )
    (net (code "38") (name "Net-(LED1-PadA)") (class "Default")
      (node (ref "LED1") (pin "A") (pinfunction "A_A") (pintype "input"))
      (node (ref "R2") (pin "1") (pinfunction "1_1") (pintype "passive"))
    )
    (net (code "39") (name "Net-(U$5-CI)") (class "Default")
      (node (ref "U$5") (pin "5") (pinfunction "CI_5") (pintype "bidirectional"))
      (node (ref "U$8") (pin "2") (pinfunction "CO_2") (pintype "bidirectional"))
    )
    (net (code "40") (name "Net-(U$5-CO)") (class "Default")
      (node (ref "U$5") (pin "2") (pinfunction "CO_2") (pintype "bidirectional"))
      (node (ref "U$6") (pin "5") (pinfunction "CI_5") (pintype "bidirectional"))
    )
    (net (code "41") (name "Net-(U$5-DI)") (class "Default")
      (node (ref "U$5") (pin "4") (pinfunction "DI_4") (pintype "bidirectional"))
      (node (ref "U$8") (pin "3") (pinfunction "DO_3") (pintype "bidirectional"))
    )
    (net (code "42") (name "Net-(U$5-DO)") (class "Default")
      (node (ref "U$5") (pin "3") (pinfunction "DO_3") (pintype "bidirectional"))
      (node (ref "U$6") (pin "4") (pinfunction "DI_4") (pintype "bidirectional"))
    )
    (net (code "43") (name "Net-(U$6-CO)") (class "Default")
      (node (ref "U$6") (pin "2") (pinfunction "CO_2") (pintype "bidirectional"))
      (node (ref "U$7") (pin "5") (pinfunction "CI_5") (pintype "bidirectional"))
    )
    (net (code "44") (name "Net-(U$6-DO)") (class "Default")
      (node (ref "U$6") (pin "3") (pinfunction "DO_3") (pintype "bidirectional"))
      (node (ref "U$7") (pin "4") (pinfunction "DI_4") (pintype "bidirectional"))
    )
    (net (code "45") (name "Net-(U$7-CO)") (class "Default")
      (node (ref "U$7") (pin "2") (pinfunction "CO_2") (pintype "bidirectional"))
      (node (ref "U$9") (pin "5") (pinfunction "CI_5") (pintype "bidirectional"))
    )
    (net (code "46") (name "Net-(U$7-DO)") (class "Default")
      (node (ref "U$7") (pin "3") (pinfunction "DO_3") (pintype "bidirectional"))
      (node (ref "U$9") (pin "4") (pinfunction "DI_4") (pintype "bidirectional"))
    )
    (net (code "47") (name "Net-(U$10-CI)") (class "Default")
      (node (ref "U$10") (pin "5") (pinfunction "CI_5") (pintype "bidirectional"))
      (node (ref "U$9") (pin "2") (pinfunction "CO_2") (pintype "bidirectional"))
    )
    (net (code "48") (name "Net-(U$10-CO)") (class "Default")
      (node (ref "U$10") (pin "2") (pinfunction "CO_2") (pintype "bidirectional"))
      (node (ref "U$11") (pin "5") (pinfunction "CI_5") (pintype "bidirectional"))
    )
    (net (code "49") (name "Net-(U$10-DI)") (class "Default")
      (node (ref "U$10") (pin "4") (pinfunction "DI_4") (pintype "bidirectional"))
      (node (ref "U$9") (pin "3") (pinfunction "DO_3") (pintype "bidirectional"))
    )
    (net (code "50") (name "Net-(U$10-DO)") (class "Default")
      (node (ref "U$10") (pin "3") (pinfunction "DO_3") (pintype "bidirectional"))
      (node (ref "U$11") (pin "4") (pinfunction "DI_4") (pintype "bidirectional"))
    )
    (net (code "51") (name "Net-(U$11-CO)") (class "Default")
      (node (ref "U$11") (pin "2") (pinfunction "CO_2") (pintype "bidirectional"))
      (node (ref "U$12") (pin "5") (pinfunction "CI_5") (pintype "bidirectional"))
    )
    (net (code "52") (name "Net-(U$11-DO)") (class "Default")
      (node (ref "U$11") (pin "3") (pinfunction "DO_3") (pintype "bidirectional"))
      (node (ref "U$12") (pin "4") (pinfunction "DI_4") (pintype "bidirectional"))
    )
    (net (code "53") (name "Net-(U$12-CO)") (class "Default")
      (node (ref "U$12") (pin "2") (pinfunction "CO_2") (pintype "bidirectional"))
      (node (ref "U$13") (pin "5") (pinfunction "CI_5") (pintype "bidirectional"))
    )
    (net (code "54") (name "Net-(U$12-DO)") (class "Default")
      (node (ref "U$12") (pin "3") (pinfunction "DO_3") (pintype "bidirectional"))
      (node (ref "U$13") (pin "4") (pinfunction "DI_4") (pintype "bidirectional"))
    )
    (net (code "55") (name "Net-(U$13-CO)") (class "Default")
      (node (ref "U$13") (pin "2") (pinfunction "CO_2") (pintype "bidirectional"))
      (node (ref "U$14") (pin "5") (pinfunction "CI_5") (pintype "bidirectional"))
    )
    (net (code "56") (name "Net-(U$13-DO)") (class "Default")
      (node (ref "U$13") (pin "3") (pinfunction "DO_3") (pintype "bidirectional"))
      (node (ref "U$14") (pin "4") (pinfunction "DI_4") (pintype "bidirectional"))
    )
    (net (code "57") (name "Net-(U$14-CO)") (class "Default")
      (node (ref "U$14") (pin "2") (pinfunction "CO_2") (pintype "bidirectional"))
      (node (ref "U$15") (pin "5") (pinfunction "CI_5") (pintype "bidirectional"))
    )
    (net (code "58") (name "Net-(U$14-DO)") (class "Default")
      (node (ref "U$14") (pin "3") (pinfunction "DO_3") (pintype "bidirectional"))
      (node (ref "U$15") (pin "4") (pinfunction "DI_4") (pintype "bidirectional"))
    )
    (net (code "59") (name "Net-(U$15-CO)") (class "Default")
      (node (ref "U$15") (pin "2") (pinfunction "CO_2") (pintype "bidirectional"))
      (node (ref "U$16") (pin "5") (pinfunction "CI_5") (pintype "bidirectional"))
    )
    (net (code "60") (name "Net-(U$15-DO)") (class "Default")
      (node (ref "U$15") (pin "3") (pinfunction "DO_3") (pintype "bidirectional"))
      (node (ref "U$16") (pin "4") (pinfunction "DI_4") (pintype "bidirectional"))
    )
    (net (code "61") (name "Net-(U$16-CO)") (class "Default")
      (node (ref "U$16") (pin "2") (pinfunction "CO_2") (pintype "bidirectional"))
      (node (ref "U$17") (pin "5") (pinfunction "CI_5") (pintype "bidirectional"))
    )
    (net (code "62") (name "Net-(U$16-DO)") (class "Default")
      (node (ref "U$16") (pin "3") (pinfunction "DO_3") (pintype "bidirectional"))
      (node (ref "U$17") (pin "4") (pinfunction "DI_4") (pintype "bidirectional"))
    )
    (net (code "63") (name "Net-(U$17-CO)") (class "Default")
      (node (ref "U$17") (pin "2") (pinfunction "CO_2") (pintype "bidirectional"))
      (node (ref "U$18") (pin "5") (pinfunction "CI_5") (pintype "bidirectional"))
    )
    (net (code "64") (name "Net-(U$17-DO)") (class "Default")
      (node (ref "U$17") (pin "3") (pinfunction "DO_3") (pintype "bidirectional"))
      (node (ref "U$18") (pin "4") (pinfunction "DI_4") (pintype "bidirectional"))
    )
    (net (code "65") (name "Net-(U$18-CO)") (class "Default")
      (node (ref "U$18") (pin "2") (pinfunction "CO_2") (pintype "bidirectional"))
      (node (ref "U$19") (pin "5") (pinfunction "CI_5") (pintype "bidirectional"))
    )
    (net (code "66") (name "Net-(U$18-DO)") (class "Default")
      (node (ref "U$18") (pin "3") (pinfunction "DO_3") (pintype "bidirectional"))
      (node (ref "U$19") (pin "4") (pinfunction "DI_4") (pintype "bidirectional"))
    )
    (net (code "67") (name "Net-(U$19-CO)") (class "Default")
      (node (ref "U$19") (pin "2") (pinfunction "CO_2") (pintype "bidirectional"))
      (node (ref "U$20") (pin "5") (pinfunction "CI_5") (pintype "bidirectional"))
    )
    (net (code "68") (name "Net-(U$19-DO)") (class "Default")
      (node (ref "U$19") (pin "3") (pinfunction "DO_3") (pintype "bidirectional"))
      (node (ref "U$20") (pin "4") (pinfunction "DI_4") (pintype "bidirectional"))
    )
    (net (code "69") (name "Net-(VDO-EN)") (class "Default")
      (node (ref "P1") (pin "C") (pinfunction "C_C") (pintype "bidirectional"))
      (node (ref "VDO") (pin "1") (pinfunction "EN_1") (pintype "passive"))
    )
    (net (code "70") (name "OSC_IN") (class "Default")
      (node (ref "C16") (pin "2") (pinfunction "2_2") (pintype "passive"))
      (node (ref "IC1") (pin "5") (pinfunction "PH0-OSC_IN_5") (pintype "passive"))
      (node (ref "R9") (pin "2") (pinfunction "2_2") (pintype "passive"))
      (node (ref "Y1") (pin "2") (pinfunction "2_2") (pintype "passive"))
    )
    (net (code "71") (name "OSC_OUT") (class "Default")
      (node (ref "C15") (pin "2") (pinfunction "2_2") (pintype "passive"))
      (node (ref "IC1") (pin "6") (pinfunction "PH1-OSC_OUT_6") (pintype "passive"))
      (node (ref "R9") (pin "1") (pinfunction "1_1") (pintype "passive"))
      (node (ref "Y1") (pin "1") (pinfunction "1_1") (pintype "passive"))
    )
    (net (code "72") (name "PA0") (class "Default")
      (node (ref "IC1") (pin "14") (pinfunction "PA0_14") (pintype "passive"))
      (node (ref "STM32-BREAKOUT") (pin "23") (pinfunction "23_23") (pintype "passive"))
    )
    (net (code "73") (name "PA1") (class "Default")
      (node (ref "IC1") (pin "15") (pinfunction "PA1_15") (pintype "passive"))
      (node (ref "STM32-BREAKOUT") (pin "25") (pinfunction "25_25") (pintype "passive"))
    )
    (net (code "74") (name "PA2") (class "Default")
      (node (ref "IC1") (pin "16") (pinfunction "PA2_16") (pintype "passive"))
      (node (ref "STM32-BREAKOUT") (pin "27") (pinfunction "27_27") (pintype "passive"))
    )
    (net (code "75") (name "PA3") (class "Default")
      (node (ref "IC1") (pin "17") (pinfunction "PA3_17") (pintype "passive"))
      (node (ref "STM32-BREAKOUT") (pin "29") (pinfunction "29_29") (pintype "passive"))
    )
    (net (code "76") (name "PA4") (class "Default")
      (node (ref "IC1") (pin "20") (pinfunction "PA4_20") (pintype "passive"))
      (node (ref "STM32-BREAKOUT") (pin "31") (pinfunction "31_31") (pintype "passive"))
    )
    (net (code "77") (name "PA5") (class "Default")
      (node (ref "IC1") (pin "21") (pinfunction "PA5_21") (pintype "passive"))
      (node (ref "STM32-BREAKOUT") (pin "33") (pinfunction "33_33") (pintype "passive"))
    )
    (net (code "78") (name "PA6") (class "Default")
      (node (ref "IC1") (pin "22") (pinfunction "PA6_22") (pintype "passive"))
      (node (ref "STM32-BREAKOUT") (pin "35") (pinfunction "35_35") (pintype "passive"))
    )
    (net (code "79") (name "PA7") (class "Default")
      (node (ref "IC1") (pin "23") (pinfunction "PA7_23") (pintype "passive"))
      (node (ref "STM32-BREAKOUT") (pin "37") (pinfunction "37_37") (pintype "passive"))
    )
    (net (code "80") (name "PA15") (class "Default")
      (node (ref "IC1") (pin "50") (pinfunction "PA15_50") (pintype "passive"))
      (node (ref "STM32-BREAKOUT") (pin "10") (pinfunction "10_10") (pintype "passive"))
    )
    (net (code "81") (name "PB0") (class "Default")
      (node (ref "IC1") (pin "26") (pinfunction "PB0_26") (pintype "passive"))
      (node (ref "STM32-BREAKOUT") (pin "38") (pinfunction "38_38") (pintype "passive"))
    )
    (net (code "82") (name "PB1") (class "Default")
      (node (ref "IC1") (pin "27") (pinfunction "PB1_27") (pintype "passive"))
      (node (ref "STM32-BREAKOUT") (pin "36") (pinfunction "36_36") (pintype "passive"))
    )
    (net (code "83") (name "PB3") (class "Default")
      (node (ref "IC1") (pin "55") (pinfunction "PB3_55") (pintype "passive"))
      (node (ref "M10") (pin "2") (pinfunction "2_2") (pintype "passive"))
    )
    (net (code "84") (name "PB4") (class "Default")
      (node (ref "IC1") (pin "56") (pinfunction "PB4_56") (pintype "passive"))
      (node (ref "M10") (pin "3") (pinfunction "3_3") (pintype "passive"))
    )
    (net (code "85") (name "PB5") (class "Default")
      (node (ref "IC1") (pin "57") (pinfunction "PB5_57") (pintype "passive"))
      (node (ref "M10") (pin "4") (pinfunction "4_4") (pintype "passive"))
    )
    (net (code "86") (name "PB6") (class "Default")
      (node (ref "IC1") (pin "58") (pinfunction "PB6_58") (pintype "passive"))
      (node (ref "M10") (pin "5") (pinfunction "5_5") (pintype "passive"))
    )
    (net (code "87") (name "PB7") (class "Default")
      (node (ref "IC1") (pin "59") (pinfunction "PB7_59") (pintype "passive"))
      (node (ref "M10") (pin "6") (pinfunction "6_6") (pintype "passive"))
    )
    (net (code "88") (name "PB8") (class "Default")
      (node (ref "IC1") (pin "61") (pinfunction "PB8_61") (pintype "passive"))
      (node (ref "M10") (pin "7") (pinfunction "7_7") (pintype "passive"))
    )
    (net (code "89") (name "PB9") (class "Default")
      (node (ref "IC1") (pin "62") (pinfunction "PB9_62") (pintype "passive"))
      (node (ref "M10") (pin "8") (pinfunction "8_8") (pintype "passive"))
    )
    (net (code "90") (name "PB13") (class "Default")
      (node (ref "IC1") (pin "34") (pinfunction "PB13_34") (pintype "passive"))
      (node (ref "STM32-BREAKOUT") (pin "21") (pinfunction "21_21") (pintype "passive"))
    )
    (net (code "91") (name "PB14") (class "Default")
      (node (ref "IC1") (pin "35") (pinfunction "PB14_35") (pintype "passive"))
      (node (ref "STM32-BREAKOUT") (pin "28") (pinfunction "28_28") (pintype "passive"))
    )
    (net (code "92") (name "PB15") (class "Default")
      (node (ref "IC1") (pin "36") (pinfunction "PB15_36") (pintype "passive"))
      (node (ref "STM32-BREAKOUT") (pin "26") (pinfunction "26_26") (pintype "passive"))
    )
    (net (code "93") (name "PC2") (class "Default")
      (node (ref "IC1") (pin "10") (pinfunction "PC2_10") (pintype "passive"))
      (node (ref "STM32-BREAKOUT") (pin "17") (pinfunction "17_17") (pintype "passive"))
    )
    (net (code "94") (name "PC6") (class "Default")
      (node (ref "IC1") (pin "37") (pinfunction "PC6_37") (pintype "passive"))
      (node (ref "STM32-BREAKOUT") (pin "24") (pinfunction "24_24") (pintype "passive"))
    )
    (net (code "95") (name "PC7") (class "Default")
      (node (ref "IC1") (pin "38") (pinfunction "PC7_38") (pintype "passive"))
      (node (ref "STM32-BREAKOUT") (pin "22") (pinfunction "22_22") (pintype "passive"))
    )
    (net (code "96") (name "PC8") (class "Default")
      (node (ref "IC1") (pin "39") (pinfunction "PC8_39") (pintype "passive"))
      (node (ref "STM32-BREAKOUT") (pin "20") (pinfunction "20_20") (pintype "passive"))
    )
    (net (code "97") (name "PC10") (class "Default")
      (node (ref "IC1") (pin "51") (pinfunction "PC10_51") (pintype "passive"))
      (node (ref "STM32-BREAKOUT") (pin "8") (pinfunction "8_8") (pintype "passive"))
    )
    (net (code "98") (name "PC13") (class "Default")
      (node (ref "C19") (pin "1") (pinfunction "1_1") (pintype "passive"))
      (node (ref "IC1") (pin "2") (pinfunction "PC13_2") (pintype "passive"))
      (node (ref "R7") (pin "2") (pinfunction "2_2") (pintype "passive"))
      (node (ref "STM32-BREAKOUT") (pin "3") (pinfunction "3_3") (pintype "passive"))
      (node (ref "STMUSER") (pin "P$2") (pinfunction "C_P$2") (pintype "passive"))
    )
    (net (code "99") (name "PC14") (class "Default")
      (node (ref "IC1") (pin "3") (pinfunction "PC14-OSC32_IN_3") (pintype "passive"))
      (node (ref "STM32-BREAKOUT") (pin "5") (pinfunction "5_5") (pintype "passive"))
    )
    (net (code "100") (name "PC15") (class "Default")
      (node (ref "IC1") (pin "4") (pinfunction "PC15-OSC32_OUT_4") (pintype "passive"))
      (node (ref "STM32-BREAKOUT") (pin "7") (pinfunction "7_7") (pintype "passive"))
    )
    (net (code "101") (name "SD1") (class "Default")
      (node (ref "ESP-BREAKOUT") (pin "22") (pinfunction "22_22") (pintype "passive"))
      (node (ref "U1") (pin "22") (pinfunction "SD1_22") (pintype "bidirectional"))
    )
    (net (code "102") (name "SD2") (class "Default")
      (node (ref "ESP-BREAKOUT") (pin "17") (pinfunction "17_17") (pintype "passive"))
      (node (ref "U1") (pin "17") (pinfunction "SD2_17") (pintype "bidirectional"))
    )
    (net (code "103") (name "SD3") (class "Default")
      (node (ref "ESP-BREAKOUT") (pin "18") (pinfunction "18_18") (pintype "passive"))
      (node (ref "U1") (pin "18") (pinfunction "SD3_18") (pintype "bidirectional"))
    )
    (net (code "104") (name "SDO") (class "Default")
      (node (ref "ESP-BREAKOUT") (pin "21") (pinfunction "21_21") (pintype "passive"))
      (node (ref "U1") (pin "21") (pinfunction "SDO_21") (pintype "bidirectional"))
    )
    (net (code "105") (name "SD_CS") (class "Default")
      (node (ref "IC1") (pin "24") (pinfunction "PC4_24") (pintype "passive"))
      (node (ref "STM32-BREAKOUT") (pin "39") (pinfunction "39_39") (pintype "passive"))
      (node (ref "U$1") (pin "SD_CS") (pinfunction "SD_CS_SD_CS") (pintype "bidirectional"))
    )
    (net (code "106") (name "SENSOR_VN") (class "Default")
      (node (ref "ESP-BREAKOUT") (pin "5") (pinfunction "5_5") (pintype "passive"))
      (node (ref "U1") (pin "5") (pinfunction "SENSOR_VN_5") (pintype "bidirectional"))
    )
    (net (code "107") (name "SENSOR_VP") (class "Default")
      (node (ref "ESP-BREAKOUT") (pin "4") (pinfunction "4_4") (pintype "passive"))
      (node (ref "U1") (pin "4") (pinfunction "SENSOR_VP_4") (pintype "bidirectional"))
    )
    (net (code "108") (name "SPI2_LCD_MOSI") (class "Default")
      (node (ref "IC1") (pin "11") (pinfunction "PC3_11") (pintype "passive"))
      (node (ref "STM32-BREAKOUT") (pin "19") (pinfunction "19_19") (pintype "passive"))
      (node (ref "U$1") (pin "SDA") (pinfunction "SDA_SDA") (pintype "bidirectional"))
    )
    (net (code "109") (name "SPI2_LCD_SCK") (class "Default")
      (node (ref "IC1") (pin "29") (pinfunction "PB10_29") (pintype "passive"))
      (node (ref "STM32-BREAKOUT") (pin "32") (pinfunction "32_32") (pintype "passive"))
      (node (ref "U$1") (pin "SCK") (pinfunction "SCK_SCK") (pintype "bidirectional"))
    )
    (net (code "110") (name "SPI3_ESP_MISO") (class "Default")
      (node (ref "ESP-BREAKOUT") (pin "16") (pinfunction "16_16") (pintype "passive"))
      (node (ref "IC1") (pin "52") (pinfunction "PC11_52") (pintype "passive"))
      (node (ref "STM32-BREAKOUT") (pin "6") (pinfunction "6_6") (pintype "passive"))
      (node (ref "U$1") (pin "SD_MISO") (pinfunction "SD_MISO_SD_MISO") (pintype "bidirectional"))
      (node (ref "U1") (pin "16") (pinfunction "IO13_16") (pintype "bidirectional"))
    )
    (net (code "111") (name "SPI3_ESP_MOSI") (class "Default")
      (node (ref "ESP-BREAKOUT") (pin "14") (pinfunction "14_14") (pintype "passive"))
      (node (ref "IC1") (pin "53") (pinfunction "PC12_53") (pintype "passive"))
      (node (ref "STM32-BREAKOUT") (pin "4") (pinfunction "4_4") (pintype "passive"))
      (node (ref "U$1") (pin "SD_MOSI") (pinfunction "SD_MOSI_SD_MOSI") (pintype "bidirectional"))
      (node (ref "U1") (pin "14") (pinfunction "IO12_14") (pintype "bidirectional"))
    )
    (net (code "112") (name "SPI3_ESP_SCK") (class "Default")
      (node (ref "ESP-BREAKOUT") (pin "23") (pinfunction "23_23") (pintype "passive"))
      (node (ref "IC1") (pin "33") (pinfunction "PB12_33") (pintype "passive"))
      (node (ref "STM32-BREAKOUT") (pin "30") (pinfunction "30_30") (pintype "passive"))
      (node (ref "U$1") (pin "SD_SCK") (pinfunction "SD_SCK_SD_SCK") (pintype "bidirectional"))
      (node (ref "U1") (pin "23") (pinfunction "IO15_23") (pintype "bidirectional"))
    )
    (net (code "113") (name "SYS_JTCK_SWCLK") (class "Default")
      (node (ref "IC1") (pin "49") (pinfunction "PA14_49") (pintype "passive"))
      (node (ref "LINK1") (pin "SWDCLK") (pinfunction "SWDCLK_SWDCLK") (pintype "input"))
    )
    (net (code "114") (name "SYS_JTMS_SWDIO") (class "Default")
      (node (ref "IC1") (pin "46") (pinfunction "PA13_46") (pintype "passive"))
      (node (ref "LINK1") (pin "SWDIO") (pinfunction "SWDIO_SWDIO") (pintype "bidirectional"))
    )
    (net (code "115") (name "USART1_RX") (class "Default")
      (node (ref "IC1") (pin "43") (pinfunction "PA10_43") (pintype "passive"))
      (node (ref "STM32-BREAKOUT") (pin "12") (pinfunction "12_12") (pintype "passive"))
    )
    (net (code "116") (name "USART1_TX") (class "Default")
      (node (ref "IC1") (pin "42") (pinfunction "PA9_42") (pintype "passive"))
      (node (ref "STM32-BREAKOUT") (pin "14") (pinfunction "14_14") (pintype "passive"))
    )
    (net (code "117") (name "USB_DM") (class "Default")
      (node (ref "IC1") (pin "44") (pinfunction "PA11_44") (pintype "passive"))
      (node (ref "USB") (pin "D+") (pinfunction "D+_D+") (pintype "bidirectional"))
    )
    (net (code "118") (name "USB_DP") (class "Default")
      (node (ref "IC1") (pin "45") (pinfunction "PA12_45") (pintype "passive"))
      (node (ref "USB") (pin "D-") (pinfunction "D-_D-") (pintype "bidirectional"))
    )
    (net (code "119") (name "VCC") (class "Default")
      (node (ref "C10") (pin "1") (pinfunction "1_1") (pintype "passive"))
      (node (ref "C13") (pin "1") (pinfunction "1_1") (pintype "passive"))
      (node (ref "C4") (pin "1") (pinfunction "1_1") (pintype "passive"))
      (node (ref "C5") (pin "1") (pinfunction "1_1") (pintype "passive"))
      (node (ref "C6") (pin "1") (pinfunction "1_1") (pintype "passive"))
      (node (ref "C7") (pin "1") (pinfunction "1_1") (pintype "passive"))
      (node (ref "C8") (pin "1") (pinfunction "1_1") (pintype "passive"))
      (node (ref "C9") (pin "1") (pinfunction "1_1") (pintype "passive"))
      (node (ref "ESP-BREAKOUT") (pin "2") (pinfunction "2_2") (pintype "passive"))
      (node (ref "FB1") (pin "1") (pinfunction "1_1") (pintype "passive"))
      (node (ref "IC1") (pin "1") (pinfunction "VBAT_1") (pintype "passive"))
      (node (ref "IC1") (pin "19") (pinfunction "VDD(1)_19") (pintype "passive"))
      (node (ref "IC1") (pin "32") (pinfunction "VDD(2)_32") (pintype "passive"))
      (node (ref "IC1") (pin "48") (pinfunction "VDD(3)_48") (pintype "passive"))
      (node (ref "IC1") (pin "64") (pinfunction "VDD(4)_64") (pintype "passive"))
      (node (ref "M10") (pin "10") (pinfunction "10_10") (pintype "passive"))
      (node (ref "R1") (pin "2") (pinfunction "2_2") (pintype "passive"))
      (node (ref "R4") (pin "2") (pinfunction "2_2") (pintype "passive"))
      (node (ref "R7") (pin "1") (pinfunction "1_1") (pintype "passive"))
      (node (ref "R8") (pin "1") (pinfunction "1_1") (pintype "passive"))
      (node (ref "STM32-BREAKOUT") (pin "1") (pinfunction "1_1") (pintype "passive"))
      (node (ref "U$1") (pin "VCC") (pinfunction "VCC_VCC") (pintype "bidirectional"))
      (node (ref "U1") (pin "2") (pinfunction "3V3_2") (pintype "bidirectional"))
      (node (ref "VDO") (pin "4") (pinfunction "VOUT_4") (pintype "passive"))
    )
    (net (code "120") (name "VCC0") (class "Default")
      (node (ref "C2") (pin "1") (pinfunction "1_1") (pintype "passive"))
      (node (ref "CHARGING_CIRCUT") (pin "4") (pinfunction "VDD_4") (pintype "bidirectional"))
      (node (ref "R2") (pin "2") (pinfunction "2_2") (pintype "passive"))
      (node (ref "USB") (pin "+5V") (pinfunction "+5V_+5V") (pintype "bidirectional"))
    )
    (net (code "121") (name "VCC1") (class "Default")
      (node (ref "C1") (pin "1") (pinfunction "1_1") (pintype "passive"))
      (node (ref "CHARGING_CIRCUT") (pin "3") (pinfunction "VBAT_3") (pintype "bidirectional"))
      (node (ref "CN1") (pin "1") (pinfunction "2_1") (pintype "passive"))
      (node (ref "RESETTABLE-FUSE") (pin "1") (pinfunction "1_1") (pintype "bidirectional"))
    )
    (net (code "122") (name "VDDA") (class "Default")
      (node (ref "C11") (pin "1") (pinfunction "1_1") (pintype "passive"))
      (node (ref "C12") (pin "1") (pinfunction "1_1") (pintype "passive"))
      (node (ref "FB1") (pin "2") (pinfunction "2_2") (pintype "passive"))
      (node (ref "IC1") (pin "13") (pinfunction "VDDA/VREF+_13") (pintype "passive"))
    )
    (net (code "123") (name "VIN") (class "Default")
      (node (ref "C14") (pin "1") (pinfunction "1_1") (pintype "passive"))
      (node (ref "C20") (pin "1") (pinfunction "1_1") (pintype "passive"))
      (node (ref "C21") (pin "1") (pinfunction "1_1") (pintype "passive"))
      (node (ref "C22") (pin "1") (pinfunction "1_1") (pintype "passive"))
      (node (ref "C23") (pin "1") (pinfunction "1_1") (pintype "passive"))
      (node (ref "C24") (pin "1") (pinfunction "1_1") (pintype "passive"))
      (node (ref "C25") (pin "1") (pinfunction "1_1") (pintype "passive"))
      (node (ref "C26") (pin "1") (pinfunction "1_1") (pintype "passive"))
      (node (ref "C27") (pin "1") (pinfunction "1_1") (pintype "passive"))
      (node (ref "C28") (pin "1") (pinfunction "1_1") (pintype "passive"))
      (node (ref "C29") (pin "1") (pinfunction "1_1") (pintype "passive"))
      (node (ref "C3") (pin "2") (pinfunction "2_2") (pintype "passive"))
      (node (ref "C30") (pin "1") (pinfunction "1_1") (pintype "passive"))
      (node (ref "C31") (pin "1") (pinfunction "1_1") (pintype "passive"))
      (node (ref "C32") (pin "1") (pinfunction "1_1") (pintype "passive"))
      (node (ref "C33") (pin "1") (pinfunction "1_1") (pintype "passive"))
      (node (ref "C34") (pin "1") (pinfunction "1_1") (pintype "passive"))
      (node (ref "ESP32PH") (pin "VCC") (pinfunction "VCC_VCC") (pintype "power_in"))
      (node (ref "LINK1") (pin "VCC") (pinfunction "VCC_VCC") (pintype "power_in"))
      (node (ref "P1") (pin "2") (pinfunction "2_2") (pintype "bidirectional"))
      (node (ref "RESETTABLE-FUSE") (pin "2") (pinfunction "2_2") (pintype "bidirectional"))
      (node (ref "U$10") (pin "1") (pinfunction "VCC_1") (pintype "bidirectional"))
      (node (ref "U$11") (pin "1") (pinfunction "VCC_1") (pintype "bidirectional"))
      (node (ref "U$12") (pin "1") (pinfunction "VCC_1") (pintype "bidirectional"))
      (node (ref "U$13") (pin "1") (pinfunction "VCC_1") (pintype "bidirectional"))
      (node (ref "U$14") (pin "1") (pinfunction "VCC_1") (pintype "bidirectional"))
      (node (ref "U$15") (pin "1") (pinfunction "VCC_1") (pintype "bidirectional"))
      (node (ref "U$16") (pin "1") (pinfunction "VCC_1") (pintype "bidirectional"))
      (node (ref "U$17") (pin "1") (pinfunction "VCC_1") (pintype "bidirectional"))
      (node (ref "U$18") (pin "1") (pinfunction "VCC_1") (pintype "bidirectional"))
      (node (ref "U$19") (pin "1") (pinfunction "VCC_1") (pintype "bidirectional"))
      (node (ref "U$20") (pin "1") (pinfunction "VCC_1") (pintype "bidirectional"))
      (node (ref "U$5") (pin "1") (pinfunction "VCC_1") (pintype "bidirectional"))
      (node (ref "U$6") (pin "1") (pinfunction "VCC_1") (pintype "bidirectional"))
      (node (ref "U$7") (pin "1") (pinfunction "VCC_1") (pintype "bidirectional"))
      (node (ref "U$8") (pin "1") (pinfunction "VCC_1") (pintype "bidirectional"))
      (node (ref "U$9") (pin "1") (pinfunction "VCC_1") (pintype "bidirectional"))
      (node (ref "VDO") (pin "6") (pinfunction "VIN_6") (pintype "passive"))
    )
    (net (code "124") (name "unconnected-(ESP-BREAKOUT-Pad3)") (class "Default")
      (node (ref "ESP-BREAKOUT") (pin "3") (pinfunction "3_3") (pintype "passive"))
    )
    (net (code "125") (name "unconnected-(ESP-BREAKOUT-Pad32)") (class "Default")
      (node (ref "ESP-BREAKOUT") (pin "32") (pinfunction "32_32") (pintype "passive"))
    )
    (net (code "126") (name "unconnected-(ESP-BREAKOUT-Pad39)") (class "Default")
      (node (ref "ESP-BREAKOUT") (pin "39") (pinfunction "39_39") (pintype "passive"))
    )
    (net (code "127") (name "unconnected-(ESP-BREAKOUT-Pad40)") (class "Default")
      (node (ref "ESP-BREAKOUT") (pin "40") (pinfunction "40_40") (pintype "passive"))
    )
    (net (code "128") (name "unconnected-(U$20-CO-Pad2)") (class "Default")
      (node (ref "U$20") (pin "2") (pinfunction "CO_2") (pintype "bidirectional"))
    )
    (net (code "129") (name "unconnected-(U$20-DO-Pad3)") (class "Default")
      (node (ref "U$20") (pin "3") (pinfunction "DO_3") (pintype "bidirectional"))
    )
    (net (code "130") (name "unconnected-(U1-NC-Pad32)") (class "Default")
      (node (ref "U1") (pin "32") (pinfunction "NC_32") (pintype "bidirectional"))
    )
    (net (code "131") (name "unconnected-(USB-PadID)") (class "Default")
      (node (ref "USB") (pin "ID") (pinfunction "ID_ID") (pintype "bidirectional"))
    )
    (net (code "132") (name "unconnected-(VDO-NC-Pad5)") (class "Default")
      (node (ref "VDO") (pin "5") (pinfunction "NC_5") (pintype "no_connect"))
    )
    (net (code "133") (name "unconnected-(VDO-PG-Pad3)") (class "Default")
      (node (ref "VDO") (pin "3") (pinfunction "PG_3") (pintype "passive"))
    )
  )
)
